# BattRead.net
KiCad netlist of a schematic drawn in Altium Designer
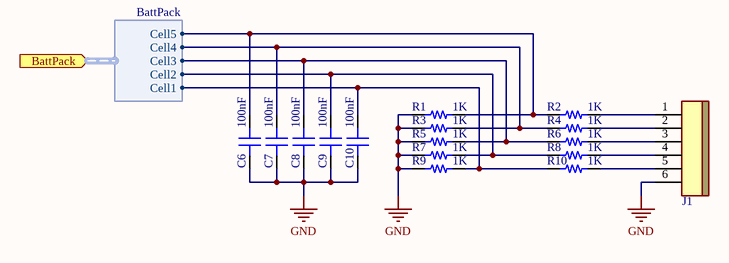
[diagram p0: BattRead.SchDoc]

(export (version "E")
  (design (tool "Eeschema 10.0.6"))
  (components
    (comp (ref "C6")
      (value "100nF")
      (footprint "CAP 0603_1608")
      (description "SMT Capacitor")
      (libsource (lib "Capacitor") (part "Cap 0603"))
    )
    (comp (ref "C7")
      (value "100nF")
      (footprint "CAP 0603_1608")
      (description "SMT Capacitor")
      (libsource (lib "Capacitor") (part "Cap 0603"))
    )
    (comp (ref "C8")
      (value "100nF")
      (footprint "CAP 0603_1608")
      (description "SMT Capacitor")
      (libsource (lib "Capacitor") (part "Cap 0603"))
    )
    (comp (ref "C9")
      (value "100nF")
      (footprint "CAP 0603_1608")
      (description "SMT Capacitor")
      (libsource (lib "Capacitor") (part "Cap 0603"))
    )
    (comp (ref "C10")
      (value "100nF")
      (footprint "CAP 0603_1608")
      (description "SMT Capacitor")
      (libsource (lib "Capacitor") (part "Cap 0603"))
    )
    (comp (ref "J1")
      (value "JST BxB-PH-K 6Pin")
      (footprint "JST B6B-PH-K")
      (description "Connector Header Through Hole 0.079\" (2.00mm)")
      (fields (field (name "PARTNUMBER") "B6B-PH-K-S(LF)(SN)"))
      (libsource (lib "Conn Terminal") (part "JST BxB-PH-K 6Pin"))
    )
    (comp (ref "R1")
      (value "1K")
      (footprint "RES 0603_1608")
      (description "SMT Resistor")
      (libsource (lib "Resistor") (part "Res 0603"))
    )
    (comp (ref "R2")
      (value "1K")
      (footprint "RES 0603_1608")
      (description "SMT Resistor")
      (libsource (lib "Resistor") (part "Res 0603"))
    )
    (comp (ref "R3")
      (value "1K")
      (footprint "RES 0603_1608")
      (description "SMT Resistor")
      (libsource (lib "Resistor") (part "Res 0603"))
    )
    (comp (ref "R4")
      (value "1K")
      (footprint "RES 0603_1608")
      (description "SMT Resistor")
      (libsource (lib "Resistor") (part "Res 0603"))
    )
    (comp (ref "R5")
      (value "1K")
      (footprint "RES 0603_1608")
      (description "SMT Resistor")
      (libsource (lib "Resistor") (part "Res 0603"))
    )
    (comp (ref "R6")
      (value "1K")
      (footprint "RES 0603_1608")
      (description "SMT Resistor")
      (libsource (lib "Resistor") (part "Res 0603"))
    )
    (comp (ref "R7")
      (value "1K")
      (footprint "RES 0603_1608")
      (description "SMT Resistor")
      (libsource (lib "Resistor") (part "Res 0603"))
    )
    (comp (ref "R8")
      (value "1K")
      (footprint "RES 0603_1608")
      (description "SMT Resistor")
      (libsource (lib "Resistor") (part "Res 0603"))
    )
    (comp (ref "R9")
      (value "1K")
      (footprint "RES 0603_1608")
      (description "SMT Resistor")
      (libsource (lib "Resistor") (part "Res 0603"))
    )
    (comp (ref "R10")
      (value "1K")
      (footprint "RES 0603_1608")
      (description "SMT Resistor")
      (libsource (lib "Resistor") (part "Res 0603"))
    )
  )
  (nets
    (net (code "3") (name "GND") (class "Default")
      (node (ref "C10") (pin "1") (pinfunction "1_1") (pintype "passive"))
      (node (ref "C6") (pin "1") (pinfunction "1_1") (pintype "passive"))
      (node (ref "C7") (pin "1") (pinfunction "1_1") (pintype "passive"))
      (node (ref "C8") (pin "1") (pinfunction "1_1") (pintype "passive"))
      (node (ref "C9") (pin "1") (pinfunction "1_1") (pintype "passive"))
      (node (ref "J1") (pin "6") (pinfunction "6_6") (pintype "passive"))
      (node (ref "R1") (pin "1") (pinfunction "1_1") (pintype "passive"))
      (node (ref "R3") (pin "1") (pinfunction "1_1") (pintype "passive"))
      (node (ref "R5") (pin "1") (pinfunction "1_1") (pintype "passive"))
      (node (ref "R7") (pin "1") (pinfunction "1_1") (pintype "passive"))
      (node (ref "R9") (pin "1") (pinfunction "1_1") (pintype "passive"))
    )
    (net (code "4") (name "Net-(C6-Pad2)") (class "Default")
      (node (ref "C6") (pin "2") (pinfunction "2_2") (pintype "passive"))
      (node (ref "R1") (pin "2") (pinfunction "2_2") (pintype "passive"))
      (node (ref "R2") (pin "1") (pinfunction "1_1") (pintype "passive"))
    )
    (net (code "5") (name "Net-(C7-Pad2)") (class "Default")
      (node (ref "C7") (pin "2") (pinfunction "2_2") (pintype "passive"))
      (node (ref "R3") (pin "2") (pinfunction "2_2") (pintype "passive"))
      (node (ref "R4") (pin "1") (pinfunction "1_1") (pintype "passive"))
    )
    (net (code "6") (name "Net-(C8-Pad2)") (class "Default")
      (node (ref "C8") (pin "2") (pinfunction "2_2") (pintype "passive"))
      (node (ref "R5") (pin "2") (pinfunction "2_2") (pintype "passive"))
      (node (ref "R6") (pin "1") (pinfunction "1_1") (pintype "passive"))
    )
    (net (code "7") (name "Net-(C9-Pad2)") (class "Default")
      (node (ref "C9") (pin "2") (pinfunction "2_2") (pintype "passive"))
      (node (ref "R7") (pin "2") (pinfunction "2_2") (pintype "passive"))
      (node (ref "R8") (pin "1") (pinfunction "1_1") (pintype "passive"))
    )
    (net (code "8") (name "Net-(C10-Pad2)") (class "Default")
      (node (ref "C10") (pin "2") (pinfunction "2_2") (pintype "passive"))
      (node (ref "R10") (pin "1") (pinfunction "1_1") (pintype "passive"))
      (node (ref "R9") (pin "2") (pinfunction "2_2") (pintype "passive"))
    )
    (net (code "9") (name "Net-(J1-Pad1)") (class "Default")
      (node (ref "J1") (pin "1") (pinfunction "1_1") (pintype "passive"))
      (node (ref "R2") (pin "2") (pinfunction "2_2") (pintype "passive"))
    )
    (net (code "10") (name "Net-(J1-Pad2)") (class "Default")
      (node (ref "J1") (pin "2") (pinfunction "2_2") (pintype "passive"))
      (node (ref "R4") (pin "2") (pinfunction "2_2") (pintype "passive"))
    )
    (net (code "11") (name "Net-(J1-Pad3)") (class "Default")
      (node (ref "J1") (pin "3") (pinfunction "3_3") (pintype "passive"))
      (node (ref "R6") (pin "2") (pinfunction "2_2") (pintype "passive"))
    )
    (net (code "12") (name "Net-(J1-Pad4)") (class "Default")
      (node (ref "J1") (pin "4") (pinfunction "4_4") (pintype "passive"))
      (node (ref "R8") (pin "2") (pinfunction "2_2") (pintype "passive"))
    )
    (net (code "13") (name "Net-(J1-Pad5)") (class "Default")
      (node (ref "J1") (pin "5") (pinfunction "5_5") (pintype "passive"))
      (node (ref "R10") (pin "2") (pinfunction "2_2") (pintype "passive"))
    )
  )
)
